# Intelligent_Agriculture.net
KiCad netlist of a schematic drawn in Altium Designer
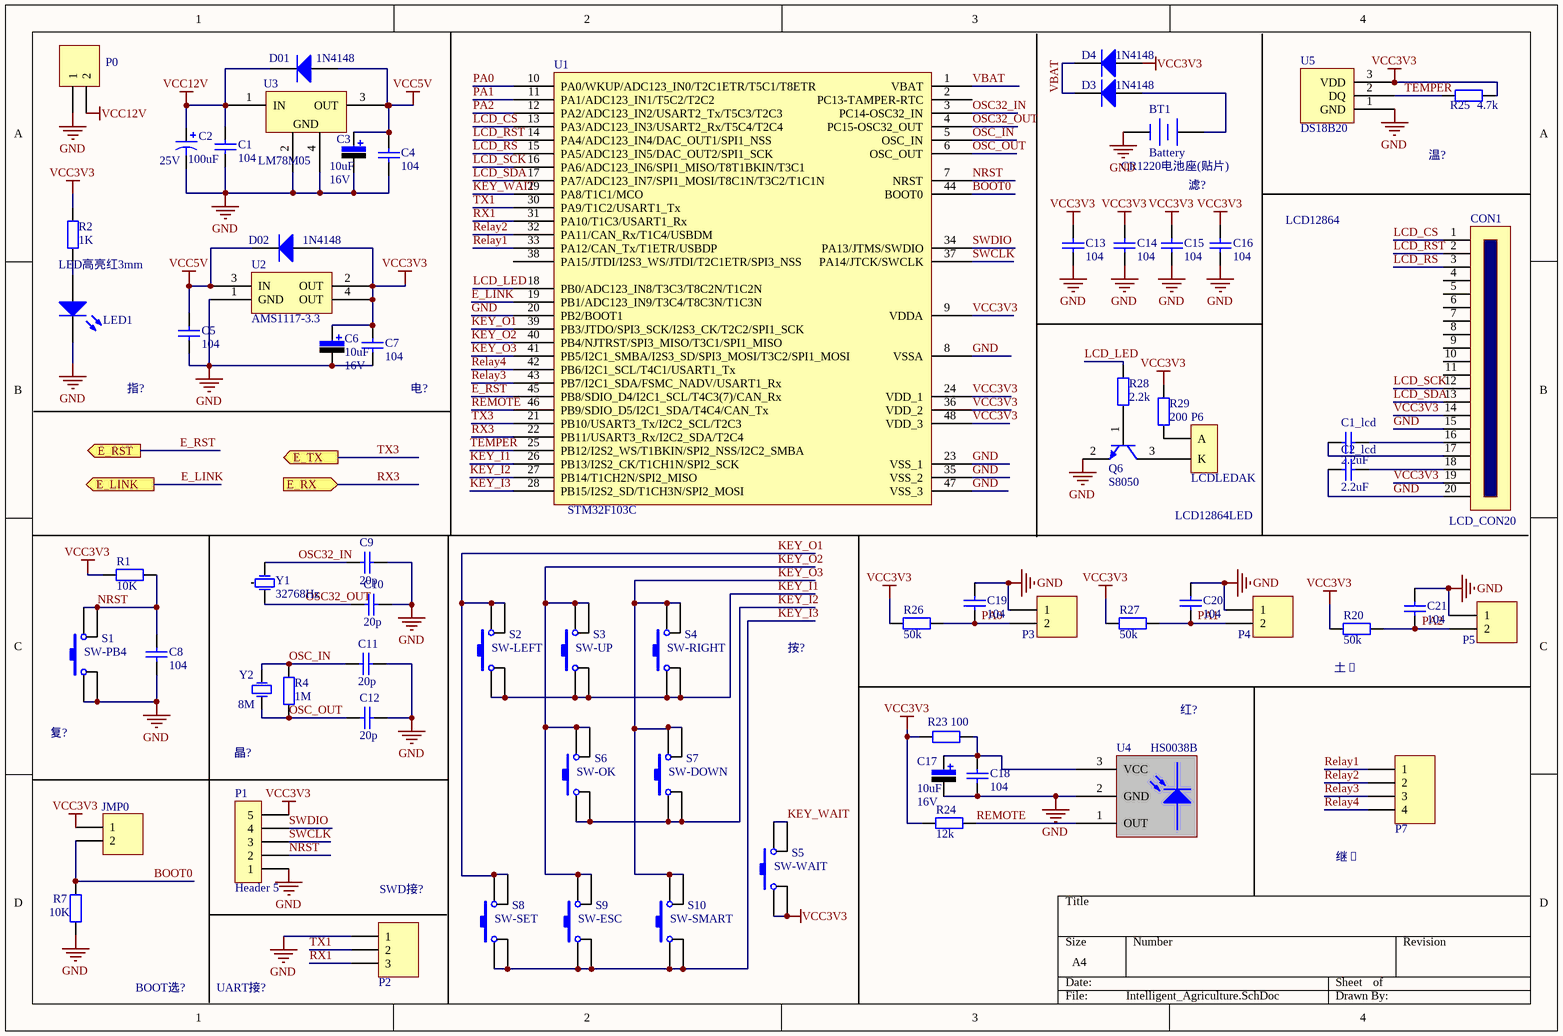
[diagram p0: Intelligent_Agriculture.SchDoc]

(export (version "E")
  (design (tool "Eeschema 10.0.6"))
  (components
    (comp (ref "BT1")
      (value "Battery")
      (description "备份电池")
      (fields (field (name "PUBLISHER") "Altium Limited"))
      (libsource (lib "fszhang") (part "Battery"))
    )
    (comp (ref "C1")
      (value "104")
      (footprint "C-RAD-0805")
      (description "无极性电容")
      (fields (field (name "Comment") "Cap") (field (name "PUBLISHER") "Altium Limited"))
      (libsource (lib "Intelligent_Agriculture_Lib") (part "Cap"))
    )
    (comp (ref "C1_lcd")
      (value "2.2uF")
      (footprint "C-RAD-0805")
      (description "无极性电容")
      (fields (field (name "Comment") "Cap") (field (name "PUBLISHER") "Altium Limited"))
      (libsource (lib "Intelligent_Agriculture_Lib") (part "Cap"))
    )
    (comp (ref "C2")
      (value "100uF")
      (footprint "C-RB-2.54")
      (description "电解电容")
      (fields
        (field (name "VOL") "25V")
        (field (name "Comment") "Cap Pol1")
        (field (name "PUBLISHER") "Altium Limited")
      )
      (libsource (lib "Miscellaneous Devices") (part "Cap Pol1"))
    )
    (comp (ref "C2_lcd")
      (value "2.2uF")
      (footprint "C-RAD-0805")
      (description "无极性电容")
      (fields (field (name "Comment") "Cap") (field (name "PUBLISHER") "Altium Limited"))
      (libsource (lib "Intelligent_Agriculture_Lib") (part "Cap"))
    )
    (comp (ref "C3")
      (value "10uF")
      (footprint "CAP-3528")
      (description "钽电容")
      (fields
        (field (name "VOL") "16V")
        (field (name "Comment") "Cap Pol")
        (field (name "PUBLISHER") "Altium Limited")
      )
      (libsource (lib "Intelligent_Agriculture_Lib") (part "Cap Pol"))
    )
    (comp (ref "C4")
      (value "104")
      (footprint "C-RAD-0805")
      (description "无极性电容")
      (fields (field (name "Comment") "Cap") (field (name "PUBLISHER") "Altium Limited"))
      (libsource (lib "Intelligent_Agriculture_Lib") (part "Cap"))
    )
    (comp (ref "C5")
      (value "104")
      (footprint "C-RAD-0805")
      (description "无极性电容")
      (fields (field (name "Comment") "Cap") (field (name "PUBLISHER") "Altium Limited"))
      (libsource (lib "Intelligent_Agriculture_Lib") (part "Cap"))
    )
    (comp (ref "C6")
      (value "10uF")
      (footprint "CAP-3528")
      (description "钽电容")
      (fields
        (field (name "VOL") "16V")
        (field (name "Comment") "Cap Pol")
        (field (name "PUBLISHER") "Altium Limited")
      )
      (libsource (lib "Intelligent_Agriculture_Lib") (part "Cap Pol"))
    )
    (comp (ref "C7")
      (value "104")
      (footprint "C-RAD-0805")
      (description "无极性电容")
      (fields (field (name "Comment") "Cap") (field (name "PUBLISHER") "Altium Limited"))
      (libsource (lib "Intelligent_Agriculture_Lib") (part "Cap"))
    )
    (comp (ref "C8")
      (value "104")
      (footprint "C-RAD-0805")
      (description "无极性电容")
      (fields (field (name "Comment") "Cap") (field (name "PUBLISHER") "Altium Limited"))
      (libsource (lib "Intelligent_Agriculture_Lib") (part "Cap"))
    )
    (comp (ref "C9")
      (value "20p")
      (footprint "C-RAD-0805")
      (description "无极性电容")
      (fields (field (name "Comment") "Cap") (field (name "PUBLISHER") "Altium Limited"))
      (libsource (lib "Intelligent_Agriculture_Lib") (part "Cap"))
    )
    (comp (ref "C10")
      (value "20p")
      (footprint "C-RAD-0805")
      (description "无极性电容")
      (fields (field (name "Comment") "Cap") (field (name "PUBLISHER") "Altium Limited"))
      (libsource (lib "Intelligent_Agriculture_Lib") (part "Cap"))
    )
    (comp (ref "C11")
      (value "20p")
      (footprint "C-RAD-0805")
      (description "无极性电容")
      (fields (field (name "Comment") "Cap") (field (name "PUBLISHER") "Altium Limited"))
      (libsource (lib "Intelligent_Agriculture_Lib") (part "Cap"))
    )
    (comp (ref "C12")
      (value "20p")
      (footprint "C-RAD-0805")
      (description "无极性电容")
      (fields (field (name "Comment") "Cap") (field (name "PUBLISHER") "Altium Limited"))
      (libsource (lib "Intelligent_Agriculture_Lib") (part "Cap"))
    )
    (comp (ref "C13")
      (value "104")
      (footprint "C-RAD-0805")
      (description "无极性电容")
      (fields (field (name "Comment") "Cap") (field (name "PUBLISHER") "Altium Limited"))
      (libsource (lib "Intelligent_Agriculture_Lib") (part "Cap"))
    )
    (comp (ref "C14")
      (value "104")
      (footprint "C-RAD-0805")
      (description "无极性电容")
      (fields (field (name "Comment") "Cap") (field (name "PUBLISHER") "Altium Limited"))
      (libsource (lib "Intelligent_Agriculture_Lib") (part "Cap"))
    )
    (comp (ref "C15")
      (value "104")
      (footprint "C-RAD-0805")
      (description "无极性电容")
      (fields (field (name "Comment") "Cap") (field (name "PUBLISHER") "Altium Limited"))
      (libsource (lib "Intelligent_Agriculture_Lib") (part "Cap"))
    )
    (comp (ref "C16")
      (value "104")
      (footprint "C-RAD-0805")
      (description "无极性电容")
      (fields (field (name "Comment") "Cap") (field (name "PUBLISHER") "Altium Limited"))
      (libsource (lib "Intelligent_Agriculture_Lib") (part "Cap"))
    )
    (comp (ref "C17")
      (value "10uF")
      (footprint "CAP-3528")
      (description "钽电容")
      (fields
        (field (name "VOL") "16V")
        (field (name "Comment") "Cap Pol")
        (field (name "PUBLISHER") "Altium Limited")
      )
      (libsource (lib "Intelligent_Agriculture_Lib") (part "Cap Pol"))
    )
    (comp (ref "C18")
      (value "104")
      (footprint "C-RAD-0805")
      (description "无极性电容")
      (fields (field (name "Comment") "Cap") (field (name "PUBLISHER") "Altium Limited"))
      (libsource (lib "Intelligent_Agriculture_Lib") (part "Cap"))
    )
    (comp (ref "C19")
      (value "104")
      (footprint "C-RAD-0805")
      (description "无极性电容")
      (fields (field (name "Comment") "Cap") (field (name "PUBLISHER") "Altium Limited"))
      (libsource (lib "Intelligent_Agriculture_Lib") (part "Cap"))
    )
    (comp (ref "C20")
      (value "104")
      (footprint "C-RAD-0805")
      (description "无极性电容")
      (fields (field (name "Comment") "Cap") (field (name "PUBLISHER") "Altium Limited"))
      (libsource (lib "Intelligent_Agriculture_Lib") (part "Cap"))
    )
    (comp (ref "C21")
      (value "104")
      (footprint "C-RAD-0805")
      (description "无极性电容")
      (fields (field (name "Comment") "Cap") (field (name "PUBLISHER") "Altium Limited"))
      (libsource (lib "Intelligent_Agriculture_Lib") (part "Cap"))
    )
    (comp (ref "CON1")
      (value "LCD_CON20")
      (footprint "FPC0.5-20P-A")
      (description "LCD接插件")
      (libsource (lib "fszhang") (part "LCD_CON20"))
    )
    (comp (ref "D01")
      (value "1N4148")
      (footprint "DIODE-1206")
      (description "二极管")
      (fields (field (name "Comment") "Diode") (field (name "PUBLISHER") "Altium Limited"))
      (libsource (lib "Intelligent_Agriculture_Lib") (part "Diode"))
    )
    (comp (ref "D02")
      (value "1N4148")
      (footprint "DIODE-1206")
      (description "二极管")
      (fields (field (name "Comment") "Diode") (field (name "PUBLISHER") "Altium Limited"))
      (libsource (lib "Intelligent_Agriculture_Lib") (part "Diode"))
    )
    (comp (ref "D3")
      (value "1N4148")
      (footprint "DIODE-1206")
      (description "二极管")
      (fields (field (name "Comment") "Diode") (field (name "PUBLISHER") "Altium Limited"))
      (libsource (lib "Intelligent_Agriculture_Lib") (part "Diode"))
    )
    (comp (ref "D4")
      (value "1N4148")
      (footprint "DIODE-1206")
      (description "二极管")
      (fields (field (name "Comment") "Diode") (field (name "PUBLISHER") "Altium Limited"))
      (libsource (lib "Intelligent_Agriculture_Lib") (part "Diode"))
    )
    (comp (ref "JMP0")
      (value "Header 2")
      (footprint "HDR2X1_A")
      (description "接插件")
      (fields (field (name "PUBLISHER") "Altium Limited"))
      (libsource (lib "fszhang") (part "Header 2"))
    )
    (comp (ref "LED1")
      (value "LED0")
      (footprint "LED_A2")
      (description "发光二极管")
      (fields (field (name "PUBLISHER") "Altium Limited"))
      (libsource (lib "Intelligent_Agriculture_Lib") (part "LED0"))
    )
    (comp (ref "P0")
      (value "Header 2")
      (footprint "HDR2X1_B1")
      (description "接插件")
      (fields (field (name "PUBLISHER") "Altium Limited"))
      (libsource (lib "") (part "Header 2_1"))
    )
    (comp (ref "P1")
      (value "Header 5")
      (footprint "HDR5_A1")
      (description "接插件")
      (fields (field (name "PUBLISHER") "Altium Limited"))
      (libsource (lib "fszhang") (part "Header 5"))
    )
    (comp (ref "P2")
      (value "Header 3")
      (footprint "HDR3X1_A")
      (description "接插件")
      (fields (field (name "PUBLISHER") "Altium Limited"))
      (libsource (lib "fszhang") (part "Header 3"))
    )
    (comp (ref "P3")
      (value "Header 2")
      (footprint "HDR2X1_B1")
      (description "接插件")
      (fields (field (name "PUBLISHER") "Altium Limited"))
      (libsource (lib "fszhang") (part "Header 2"))
    )
    (comp (ref "P4")
      (value "Header 2")
      (footprint "HDR2X1_B1")
      (description "接插件")
      (fields (field (name "PUBLISHER") "Altium Limited"))
      (libsource (lib "fszhang") (part "Header 2"))
    )
    (comp (ref "P5")
      (value "Header 2")
      (footprint "HDR2X1_B1")
      (description "接插件")
      (fields (field (name "PUBLISHER") "Altium Limited"))
      (libsource (lib "fszhang") (part "Header 2"))
    )
    (comp (ref "P6")
      (value "LCDLEDAK")
      (footprint "LCD_JLX12864G-1504")
      (description "LCD12864框架")
      (libsource (lib "fszhang") (part "LCDLEDAK"))
    )
    (comp (ref "P7")
      (value "Header 4")
      (footprint "HDR4X1_B1")
      (description "接插件")
      (fields (field (name "PUBLISHER") "Altium Limited"))
      (libsource (lib "fszhang") (part "Header 4"))
    )
    (comp (ref "Q6")
      (value "S8050")
      (description "NPN三极管")
      (fields (field (name "PUBLISHER") "Altium Limited"))
      (libsource (lib "fszhang") (part "BCP68"))
    )
    (comp (ref "R1")
      (value "10K")
      (description "贴片电阻")
      (fields (field (name "Comment") "Res1") (field (name "PUBLISHER") "Altium Limited"))
      (libsource (lib "fszhang") (part "Res1"))
    )
    (comp (ref "R2")
      (value "1K")
      (description "贴片电阻")
      (fields (field (name "Comment") "Res1") (field (name "PUBLISHER") "Altium Limited"))
      (libsource (lib "") (part "Res1_1"))
    )
    (comp (ref "R4")
      (value "1M")
      (description "贴片电阻")
      (fields (field (name "Comment") "Res1") (field (name "PUBLISHER") "Altium Limited"))
      (libsource (lib "") (part "Res1_1"))
    )
    (comp (ref "R7")
      (value "10K")
      (description "贴片电阻")
      (fields (field (name "Comment") "Res1") (field (name "PUBLISHER") "Altium Limited"))
      (libsource (lib "") (part "Res1_2"))
    )
    (comp (ref "R20")
      (value "50k")
      (description "贴片电阻")
      (fields (field (name "Comment") "Res1") (field (name "PUBLISHER") "Altium Limited"))
      (libsource (lib "fszhang") (part "Res1"))
    )
    (comp (ref "R23")
      (value "100")
      (description "贴片电阻")
      (fields (field (name "Comment") "Res1") (field (name "PUBLISHER") "Altium Limited"))
      (libsource (lib "") (part "Res1_3"))
    )
    (comp (ref "R24")
      (value "12k")
      (description "贴片电阻")
      (fields (field (name "Comment") "Res1") (field (name "PUBLISHER") "Altium Limited"))
      (libsource (lib "") (part "Res1_3"))
    )
    (comp (ref "R25")
      (value "4.7k")
      (description "贴片电阻")
      (fields (field (name "Comment") "Res1") (field (name "PUBLISHER") "Altium Limited"))
      (libsource (lib "") (part "Res1_3"))
    )
    (comp (ref "R26")
      (value "50k")
      (description "贴片电阻")
      (fields (field (name "Comment") "Res1") (field (name "PUBLISHER") "Altium Limited"))
      (libsource (lib "fszhang") (part "Res1"))
    )
    (comp (ref "R27")
      (value "50k")
      (description "贴片电阻")
      (fields (field (name "Comment") "Res1") (field (name "PUBLISHER") "Altium Limited"))
      (libsource (lib "fszhang") (part "Res1"))
    )
    (comp (ref "R28")
      (value "2.2k")
      (description "贴片电阻")
      (fields (field (name "Comment") "Res1") (field (name "PUBLISHER") "Altium Limited"))
      (libsource (lib "") (part "Res1_1"))
    )
    (comp (ref "R29")
      (value "200")
      (footprint "1206")
      (description "贴片电阻")
      (fields (field (name "Comment") "Res1") (field (name "PUBLISHER") "Altium Limited"))
      (libsource (lib "") (part "Res1_1"))
    )
    (comp (ref "S1")
      (value "SW-PB4")
      (footprint "SW_PB4_B1")
      (description "微动开关")
      (fields (field (name "PUBLISHER") "Altium Limited"))
      (libsource (lib "fszhang") (part "SW-PB4"))
    )
    (comp (ref "S2")
      (value "SW-LEFT")
      (footprint "SW_PB4_B1")
      (description "微动开关")
      (fields (field (name "PUBLISHER") "Altium Limited"))
      (libsource (lib "fszhang") (part "SW-PB4"))
    )
    (comp (ref "S3")
      (value "SW-UP")
      (footprint "SW_PB4_B1")
      (description "微动开关")
      (fields (field (name "PUBLISHER") "Altium Limited"))
      (libsource (lib "fszhang") (part "SW-PB4"))
    )
    (comp (ref "S4")
      (value "SW-RIGHT")
      (footprint "SW_PB4_B1")
      (description "微动开关")
      (fields (field (name "PUBLISHER") "Altium Limited"))
      (libsource (lib "fszhang") (part "SW-PB4"))
    )
    (comp (ref "S5")
      (value "SW-WAIT")
      (footprint "SW_PB4_B1")
      (description "微动开关")
      (fields (field (name "PUBLISHER") "Altium Limited"))
      (libsource (lib "fszhang") (part "SW-PB4"))
    )
    (comp (ref "S6")
      (value "SW-OK")
      (footprint "SW_PB4_B1")
      (description "微动开关")
      (fields (field (name "PUBLISHER") "Altium Limited"))
      (libsource (lib "fszhang") (part "SW-PB4"))
    )
    (comp (ref "S7")
      (value "SW-DOWN")
      (footprint "SW_PB4_B1")
      (description "微动开关")
      (fields (field (name "PUBLISHER") "Altium Limited"))
      (libsource (lib "fszhang") (part "SW-PB4"))
    )
    (comp (ref "S8")
      (value "SW-SET")
      (footprint "SW_PB4_B1")
      (description "微动开关")
      (fields (field (name "PUBLISHER") "Altium Limited"))
      (libsource (lib "fszhang") (part "SW-PB4"))
    )
    (comp (ref "S9")
      (value "SW-ESC")
      (footprint "SW_PB4_B1")
      (description "微动开关")
      (fields (field (name "PUBLISHER") "Altium Limited"))
      (libsource (lib "fszhang") (part "SW-PB4"))
    )
    (comp (ref "S10")
      (value "SW-SMART")
      (footprint "SW_PB4_B1")
      (description "微动开关")
      (fields (field (name "PUBLISHER") "Altium Limited"))
      (libsource (lib "fszhang") (part "SW-PB4"))
    )
    (comp (ref "U1")
      (value "STM32F103C")
      (footprint "LQFP-48_M")
      (description "STM32单片机48引脚")
      (libsource (lib "fszhang") (part "STM32F103C"))
    )
    (comp (ref "U2")
      (value "AMS1117-3.3")
      (footprint "SOT-223")
      (description "3.3V稳压芯片")
      (libsource (lib "fszhang") (part "SPX1117M3-3.3"))
    )
    (comp (ref "U3")
      (value "LM78M05")
      (footprint "TO-252")
      (description "5V稳压芯片")
      (libsource (lib "fszhang") (part "LM78M05"))
    )
    (comp (ref "U4") (value "HS0038B") (description "红外接收器") (libsource (lib "fszhang") (part "HS0038B")))
    (comp (ref "U5")
      (value "DS18B20")
      (footprint "HDR3X1_B1")
      (description "温度传感器")
      (libsource (lib "fszhang") (part "DS18B20"))
    )
    (comp (ref "Y1")
      (value "32768Hz")
      (footprint "X-TC15_B")
      (description "圆柱晶振")
      (fields (field (name "Comment") "XTAL_SM") (field (name "PUBLISHER") "Altium Limited"))
      (libsource (lib "Intelligent_Agriculture_Lib") (part "XTAL_SM"))
    )
    (comp (ref "Y2")
      (value "8M")
      (description "晶振")
      (fields (field (name "Comment") "XTAL") (field (name "PUBLISHER") "Altium Limited"))
      (libsource (lib "fszhang") (part "XTAL"))
    )
  )
  (nets
    (net (code "1") (name "/BOOT0") (class "Default")
      (node (ref "JMP0") (pin "2") (pinfunction "2_2") (pintype "passive"))
      (node (ref "R7") (pin "1") (pinfunction "1_1") (pintype "passive"))
      (node (ref "U1") (pin "44") (pinfunction "BOOT0_44") (pintype "passive"))
    )
    (net (code "2") (name "/E_LINK") (class "Default")
      (node (ref "U1") (pin "19") (pinfunction "PB1/ADC123_IN9/T3C4/T8C3N/T1C3N_19") (pintype "passive"))
    )
    (net (code "3") (name "/E_RST") (class "Default")
      (node (ref "U1") (pin "45") (pinfunction "PB8/SDIO_D4/I2C1_SCL/T4C3(7)/CAN_Rx_45") (pintype "passive"))
    )
    (net (code "4") (name "/KEY_I1") (class "Default")
      (node (ref "S2") (pin "1") (pinfunction "1_1") (pintype "passive"))
      (node (ref "S2") (pin "4") (pinfunction "4_4") (pintype "passive"))
      (node (ref "S3") (pin "1") (pinfunction "1_1") (pintype "passive"))
      (node (ref "S3") (pin "4") (pinfunction "4_4") (pintype "passive"))
      (node (ref "S4") (pin "1") (pinfunction "1_1") (pintype "passive"))
      (node (ref "S4") (pin "4") (pinfunction "4_4") (pintype "passive"))
      (node (ref "U1") (pin "26") (pinfunction "PB13/I2S2_CK/T1CH1N/SPI2_SCK_26") (pintype "passive"))
    )
    (net (code "5") (name "/KEY_I2") (class "Default")
      (node (ref "S6") (pin "1") (pinfunction "1_1") (pintype "passive"))
      (node (ref "S6") (pin "4") (pinfunction "4_4") (pintype "passive"))
      (node (ref "S7") (pin "1") (pinfunction "1_1") (pintype "passive"))
      (node (ref "S7") (pin "4") (pinfunction "4_4") (pintype "passive"))
      (node (ref "U1") (pin "27") (pinfunction "PB14/T1CH2N/SPI2_MISO_27") (pintype "passive"))
    )
    (net (code "6") (name "/KEY_I3") (class "Default")
      (node (ref "S10") (pin "1") (pinfunction "1_1") (pintype "passive"))
      (node (ref "S10") (pin "4") (pinfunction "4_4") (pintype "passive"))
      (node (ref "S8") (pin "1") (pinfunction "1_1") (pintype "passive"))
      (node (ref "S8") (pin "4") (pinfunction "4_4") (pintype "passive"))
      (node (ref "S9") (pin "1") (pinfunction "1_1") (pintype "passive"))
      (node (ref "S9") (pin "4") (pinfunction "4_4") (pintype "passive"))
      (node (ref "U1") (pin "28") (pinfunction "PB15/I2S2_SD/T1CH3N/SPI2_MOSI_28") (pintype "passive"))
    )
    (net (code "7") (name "/KEY_O1") (class "Default")
      (node (ref "S2") (pin "2") (pinfunction "2_2") (pintype "passive"))
      (node (ref "S2") (pin "3") (pinfunction "3_3") (pintype "passive"))
      (node (ref "S8") (pin "2") (pinfunction "2_2") (pintype "passive"))
      (node (ref "S8") (pin "3") (pinfunction "3_3") (pintype "passive"))
      (node (ref "U1") (pin "39") (pinfunction "PB3/JTDO/SPI3_SCK/I2S3_CK/T2C2/SPI1_SCK_39") (pintype "passive"))
    )
    (net (code "8") (name "/KEY_O2") (class "Default")
      (node (ref "S3") (pin "2") (pinfunction "2_2") (pintype "passive"))
      (node (ref "S3") (pin "3") (pinfunction "3_3") (pintype "passive"))
      (node (ref "S6") (pin "2") (pinfunction "2_2") (pintype "passive"))
      (node (ref "S6") (pin "3") (pinfunction "3_3") (pintype "passive"))
      (node (ref "S9") (pin "2") (pinfunction "2_2") (pintype "passive"))
      (node (ref "S9") (pin "3") (pinfunction "3_3") (pintype "passive"))
      (node (ref "U1") (pin "40") (pinfunction "PB4/NJTRST/SPI3_MISO/T3C1/SPI1_MISO_40") (pintype "passive"))
    )
    (net (code "9") (name "/KEY_O3") (class "Default")
      (node (ref "S10") (pin "2") (pinfunction "2_2") (pintype "passive"))
      (node (ref "S10") (pin "3") (pinfunction "3_3") (pintype "passive"))
      (node (ref "S4") (pin "2") (pinfunction "2_2") (pintype "passive"))
      (node (ref "S4") (pin "3") (pinfunction "3_3") (pintype "passive"))
      (node (ref "S7") (pin "2") (pinfunction "2_2") (pintype "passive"))
      (node (ref "S7") (pin "3") (pinfunction "3_3") (pintype "passive"))
      (node (ref "U1") (pin "41") (pinfunction "PB5/I2C1_SMBA/I2S3_SD/SPI3_MOSI/T3C2/SPI1_MOSI_41") (pintype "passive"))
    )
    (net (code "10") (name "/KEY_WAIT") (class "Default")
      (node (ref "S5") (pin "2") (pinfunction "2_2") (pintype "passive"))
      (node (ref "S5") (pin "3") (pinfunction "3_3") (pintype "passive"))
      (node (ref "U1") (pin "29") (pinfunction "PA8/T1C1/MCO_29") (pintype "passive"))
    )
    (net (code "11") (name "/LCD_CS") (class "Default")
      (node (ref "CON1") (pin "1") (pinfunction "1_1") (pintype "passive"))
      (node (ref "U1") (pin "13") (pinfunction "PA3/ADC123_IN3/USART2_Rx/T5C4/T2C4_13") (pintype "passive"))
    )
    (net (code "12") (name "/LCD_LED") (class "Default")
      (node (ref "R28") (pin "2") (pinfunction "2_2") (pintype "passive"))
      (node (ref "U1") (pin "18") (pinfunction "PB0/ADC123_IN8/T3C3/T8C2N/T1C2N_18") (pintype "passive"))
    )
    (net (code "13") (name "/LCD_RS") (class "Default")
      (node (ref "CON1") (pin "3") (pinfunction "3_3") (pintype "passive"))
      (node (ref "U1") (pin "15") (pinfunction "PA5/ADC123_IN5/DAC_OUT2/SPI1_SCK_15") (pintype "passive"))
    )
    (net (code "14") (name "/LCD_RST") (class "Default")
      (node (ref "CON1") (pin "2") (pinfunction "2_2") (pintype "passive"))
      (node (ref "U1") (pin "14") (pinfunction "PA4/ADC123_IN4/DAC_OUT1/SPI1_NSS_14") (pintype "passive"))
    )
    (net (code "15") (name "/LCD_SCK") (class "Default")
      (node (ref "CON1") (pin "12") (pinfunction "12_12") (pintype "passive"))
      (node (ref "U1") (pin "16") (pinfunction "PA6/ADC123_IN6/SPI1_MISO/T8T1BKIN/T3C1_16") (pintype "passive"))
    )
    (net (code "16") (name "/LCD_SDA") (class "Default")
      (node (ref "CON1") (pin "13") (pinfunction "13_13") (pintype "passive"))
      (node (ref "U1") (pin "17") (pinfunction "PA7/ADC123_IN7/SPI1_MOSI/T8C1N/T3C2/T1C1N_17") (pintype "passive"))
    )
    (net (code "17") (name "/NRST") (class "Default")
      (node (ref "C8") (pin "2") (pinfunction "2_2") (pintype "passive"))
      (node (ref "P1") (pin "2") (pinfunction "2_2") (pintype "passive"))
      (node (ref "R1") (pin "1") (pinfunction "1_1") (pintype "passive"))
      (node (ref "S1") (pin "2") (pinfunction "2_2") (pintype "passive"))
      (node (ref "S1") (pin "3") (pinfunction "3_3") (pintype "passive"))
      (node (ref "U1") (pin "7") (pinfunction "NRST_7") (pintype "passive"))
    )
    (net (code "18") (name "/OSC32_IN") (class "Default")
      (node (ref "C9") (pin "1") (pinfunction "1_1") (pintype "passive"))
      (node (ref "U1") (pin "3") (pinfunction "PC14-OSC32_IN_3") (pintype "passive"))
      (node (ref "Y1") (pin "1") (pinfunction "OSC1_1") (pintype "passive"))
    )
    (net (code "19") (name "/OSC32_OUT") (class "Default")
      (node (ref "C10") (pin "1") (pinfunction "1_1") (pintype "passive"))
      (node (ref "U1") (pin "4") (pinfunction "PC15-OSC32_OUT_4") (pintype "passive"))
      (node (ref "Y1") (pin "2") (pinfunction "OSC2_2") (pintype "passive"))
    )
    (net (code "20") (name "/OSC_IN") (class "Default")
      (node (ref "C11") (pin "1") (pinfunction "1_1") (pintype "passive"))
      (node (ref "R4") (pin "2") (pinfunction "2_2") (pintype "passive"))
      (node (ref "U1") (pin "5") (pinfunction "OSC_IN_5") (pintype "passive"))
      (node (ref "Y2") (pin "2") (pinfunction "OSC2_2") (pintype "passive"))
    )
    (net (code "21") (name "/OSC_OUT") (class "Default")
      (node (ref "C12") (pin "1") (pinfunction "1_1") (pintype "passive"))
      (node (ref "R4") (pin "1") (pinfunction "1_1") (pintype "passive"))
      (node (ref "U1") (pin "6") (pinfunction "OSC_OUT_6") (pintype "passive"))
      (node (ref "Y2") (pin "1") (pinfunction "OSC1_1") (pintype "passive"))
    )
    (net (code "22") (name "/PA0") (class "Default")
      (node (ref "C19") (pin "2") (pinfunction "2_2") (pintype "passive"))
      (node (ref "P3") (pin "2") (pinfunction "2_2") (pintype "passive"))
      (node (ref "R26") (pin "1") (pinfunction "1_1") (pintype "passive"))
      (node (ref "U1") (pin "10") (pinfunction "PA0/WKUP/ADC123_IN0/T2C1ETR/T5C1/T8ETR_10") (pintype "passive"))
    )
    (net (code "23") (name "/PA1") (class "Default")
      (node (ref "C20") (pin "2") (pinfunction "2_2") (pintype "passive"))
      (node (ref "P4") (pin "2") (pinfunction "2_2") (pintype "passive"))
      (node (ref "R27") (pin "1") (pinfunction "1_1") (pintype "passive"))
      (node (ref "U1") (pin "11") (pinfunction "PA1/ADC123_IN1/T5C2/T2C2_11") (pintype "passive"))
    )
    (net (code "24") (name "/PA2") (class "Default")
      (node (ref "C21") (pin "2") (pinfunction "2_2") (pintype "passive"))
      (node (ref "P5") (pin "2") (pinfunction "2_2") (pintype "passive"))
      (node (ref "R20") (pin "1") (pinfunction "1_1") (pintype "passive"))
      (node (ref "U1") (pin "12") (pinfunction "PA2/ADC123_IN2/USART2_Tx/T5C3/T2C3_12") (pintype "passive"))
    )
    (net (code "25") (name "/REMOTE") (class "Default")
      (node (ref "R24") (pin "2") (pinfunction "2_2") (pintype "passive"))
      (node (ref "U1") (pin "46") (pinfunction "PB9/SDIO_D5/I2C1_SDA/T4C4/CAN_Tx_46") (pintype "passive"))
      (node (ref "U4") (pin "1") (pinfunction "OUT_1") (pintype "passive"))
    )
    (net (code "26") (name "/RX1") (class "Default")
      (node (ref "P2") (pin "3") (pinfunction "3_3") (pintype "passive"))
      (node (ref "U1") (pin "31") (pinfunction "PA10/T1C3/USART1_Rx_31") (pintype "passive"))
    )
    (net (code "27") (name "/RX3") (class "Default")
      (node (ref "U1") (pin "22") (pinfunction "PB11/USART3_Rx/I2C2_SDA/T2C4_22") (pintype "passive"))
    )
    (net (code "28") (name "/Relay1") (class "Default")
      (node (ref "P7") (pin "1") (pinfunction "1_1") (pintype "passive"))
      (node (ref "U1") (pin "33") (pinfunction "PA12/CAN_Tx/T1ETR/USBDP_33") (pintype "passive"))
    )
    (net (code "29") (name "/Relay2") (class "Default")
      (node (ref "P7") (pin "2") (pinfunction "2_2") (pintype "passive"))
      (node (ref "U1") (pin "32") (pinfunction "PA11/CAN_Rx/T1C4/USBDM_32") (pintype "passive"))
    )
    (net (code "30") (name "/Relay3") (class "Default")
      (node (ref "P7") (pin "3") (pinfunction "3_3") (pintype "passive"))
      (node (ref "U1") (pin "43") (pinfunction "PB7/I2C1_SDA/FSMC_NADV/USART1_Rx_43") (pintype "passive"))
    )
    (net (code "31") (name "/Relay4") (class "Default")
      (node (ref "P7") (pin "4") (pinfunction "4_4") (pintype "passive"))
      (node (ref "U1") (pin "42") (pinfunction "PB6/I2C1_SCL/T4C1/USART1_Tx_42") (pintype "passive"))
    )
    (net (code "32") (name "/SWCLK") (class "Default")
      (node (ref "P1") (pin "3") (pinfunction "3_3") (pintype "passive"))
      (node (ref "U1") (pin "37") (pinfunction "PA14/JTCK/SWCLK_37") (pintype "passive"))
    )
    (net (code "33") (name "/SWDIO") (class "Default")
      (node (ref "P1") (pin "4") (pinfunction "4_4") (pintype "passive"))
      (node (ref "U1") (pin "34") (pinfunction "PA13/JTMS/SWDIO_34") (pintype "passive"))
    )
    (net (code "34") (name "/TEMPER") (class "Default")
      (node (ref "R25") (pin "1") (pinfunction "1_1") (pintype "passive"))
      (node (ref "U1") (pin "25") (pinfunction "PB12/I2S2_WS/T1BKIN/SPI2_NSS/I2C2_SMBA_25") (pintype "passive"))
      (node (ref "U5") (pin "2") (pinfunction "DQ_2") (pintype "passive"))
    )
    (net (code "35") (name "/TX1") (class "Default")
      (node (ref "P2") (pin "2") (pinfunction "2_2") (pintype "passive"))
      (node (ref "U1") (pin "30") (pinfunction "PA9/T1C2/USART1_Tx_30") (pintype "passive"))
    )
    (net (code "36") (name "/TX3") (class "Default")
      (node (ref "U1") (pin "21") (pinfunction "PB10/USART3_Tx/I2C2_SCL/T2C3_21") (pintype "passive"))
    )
    (net (code "37") (name "/VBAT") (class "Default")
      (node (ref "D3") (pin "2") (pinfunction "K_2") (pintype "passive"))
      (node (ref "D4") (pin "2") (pinfunction "K_2") (pintype "passive"))
      (node (ref "U1") (pin "1") (pinfunction "VBAT_1") (pintype "passive"))
    )
    (net (code "38") (name "GND") (class "Default")
      (node (ref "BT1") (pin "2") (pinfunction "-_2") (pintype "passive"))
      (node (ref "C1") (pin "2") (pinfunction "2_2") (pintype "passive"))
      (node (ref "C10") (pin "2") (pinfunction "2_2") (pintype "passive"))
      (node (ref "C11") (pin "2") (pinfunction "2_2") (pintype "passive"))
      (node (ref "C12") (pin "2") (pinfunction "2_2") (pintype "passive"))
      (node (ref "C13") (pin "2") (pinfunction "2_2") (pintype "passive"))
      (node (ref "C14") (pin "2") (pinfunction "2_2") (pintype "passive"))
      (node (ref "C15") (pin "2") (pinfunction "2_2") (pintype "passive"))
      (node (ref "C16") (pin "2") (pinfunction "2_2") (pintype "passive"))
      (node (ref "C17") (pin "2") (pinfunction "2_2") (pintype "passive"))
      (node (ref "C18") (pin "2") (pinfunction "2_2") (pintype "passive"))
      (node (ref "C19") (pin "1") (pinfunction "1_1") (pintype "passive"))
      (node (ref "C2") (pin "2") (pinfunction "2_2") (pintype "passive"))
      (node (ref "C20") (pin "1") (pinfunction "1_1") (pintype "passive"))
      (node (ref "C21") (pin "1") (pinfunction "1_1") (pintype "passive"))
      (node (ref "C2_lcd") (pin "2") (pinfunction "2_2") (pintype "passive"))
      (node (ref "C3") (pin "2") (pinfunction "2_2") (pintype "passive"))
      (node (ref "C4") (pin "2") (pinfunction "2_2") (pintype "passive"))
      (node (ref "C5") (pin "2") (pinfunction "2_2") (pintype "passive"))
      (node (ref "C6") (pin "2") (pinfunction "2_2") (pintype "passive"))
      (node (ref "C7") (pin "2") (pinfunction "2_2") (pintype "passive"))
      (node (ref "C8") (pin "1") (pinfunction "1_1") (pintype "passive"))
      (node (ref "C9") (pin "2") (pinfunction "2_2") (pintype "passive"))
      (node (ref "CON1") (pin "15") (pinfunction "15_15") (pintype "passive"))
      (node (ref "CON1") (pin "20") (pinfunction "20_20") (pintype "passive"))
      (node (ref "LED1") (pin "2") (pinfunction "K_2") (pintype "passive"))
      (node (ref "P0") (pin "1") (pinfunction "1_1") (pintype "passive"))
      (node (ref "P1") (pin "1") (pinfunction "1_1") (pintype "passive"))
      (node (ref "P2") (pin "1") (pinfunction "1_1") (pintype "passive"))
      (node (ref "P3") (pin "1") (pinfunction "1_1") (pintype "passive"))
      (node (ref "P4") (pin "1") (pinfunction "1_1") (pintype "passive"))
      (node (ref "P5") (pin "1") (pinfunction "1_1") (pintype "passive"))
      (node (ref "Q6") (pin "2") (pinfunction "E_2") (pintype "passive"))
      (node (ref "R7") (pin "2") (pinfunction "2_2") (pintype "passive"))
      (node (ref "S1") (pin "1") (pinfunction "1_1") (pintype "passive"))
      (node (ref "S1") (pin "4") (pinfunction "4_4") (pintype "passive"))
      (node (ref "U1") (pin "20") (pinfunction "PB2/BOOT1_20") (pintype "passive"))
      (node (ref "U1") (pin "23") (pinfunction "VSS_1_23") (pintype "passive"))
      (node (ref "U1") (pin "35") (pinfunction "VSS_2_35") (pintype "passive"))
      (node (ref "U1") (pin "47") (pinfunction "VSS_3_47") (pintype "passive"))
      (node (ref "U1") (pin "8") (pinfunction "VSSA_8") (pintype "passive"))
      (node (ref "U2") (pin "1") (pinfunction "GND_1") (pintype "passive"))
      (node (ref "U3") (pin "2") (pinfunction "GND_2") (pintype "power_in"))
      (node (ref "U3") (pin "4") (pinfunction "GND_4") (pintype "power_in"))
      (node (ref "U4") (pin "2") (pinfunction "GND_2") (pintype "passive"))
      (node (ref "U5") (pin "1") (pinfunction "GND_1") (pintype "passive"))
    )
    (net (code "39") (name "Net-(BT1-+)") (class "Default")
      (node (ref "BT1") (pin "1") (pinfunction "+_1") (pintype "passive"))
      (node (ref "D3") (pin "1") (pinfunction "A_1") (pintype "passive"))
    )
    (net (code "40") (name "Net-(C1_lcd-Pad1)") (class "Default")
      (node (ref "C1_lcd") (pin "1") (pinfunction "1_1") (pintype "passive"))
      (node (ref "CON1") (pin "16") (pinfunction "16_16") (pintype "passive"))
    )
    (net (code "41") (name "Net-(C1_lcd-Pad2)") (class "Default")
      (node (ref "C1_lcd") (pin "2") (pinfunction "2_2") (pintype "passive"))
      (node (ref "CON1") (pin "17") (pinfunction "17_17") (pintype "passive"))
    )
    (net (code "42") (name "Net-(C2_lcd-Pad1)") (class "Default")
      (node (ref "C2_lcd") (pin "1") (pinfunction "1_1") (pintype "passive"))
      (node (ref "CON1") (pin "18") (pinfunction "18_18") (pintype "passive"))
    )
    (net (code "43") (name "Net-(LED1-A)") (class "Default")
      (node (ref "LED1") (pin "1") (pinfunction "A_1") (pintype "passive"))
      (node (ref "R2") (pin "1") (pinfunction "1_1") (pintype "passive"))
    )
    (net (code "44") (name "Net-(P6-A)") (class "Default")
      (node (ref "P6") (pin "1") (pinfunction "A_1") (pintype "passive"))
      (node (ref "R29") (pin "1") (pinfunction "1_1") (pintype "passive"))
    )
    (net (code "45") (name "Net-(P6-K)") (class "Default")
      (node (ref "P6") (pin "2") (pinfunction "K_2") (pintype "passive"))
      (node (ref "Q6") (pin "3") (pinfunction "C_3") (pintype "passive"))
    )
    (net (code "46") (name "Net-(Q6-B)") (class "Default")
      (node (ref "Q6") (pin "1") (pinfunction "B_1") (pintype "passive"))
      (node (ref "R28") (pin "1") (pinfunction "1_1") (pintype "passive"))
    )
    (net (code "47") (name "Net-(U4-VCC)") (class "Default")
      (node (ref "C17") (pin "1") (pinfunction "1_1") (pintype "passive"))
      (node (ref "C18") (pin "1") (pinfunction "1_1") (pintype "passive"))
      (node (ref "R23") (pin "2") (pinfunction "2_2") (pintype "passive"))
      (node (ref "U4") (pin "3") (pinfunction "VCC_3") (pintype "passive"))
    )
    (net (code "48") (name "VCC3V3") (class "Default")
      (node (ref "C13") (pin "1") (pinfunction "1_1") (pintype "passive"))
      (node (ref "C14") (pin "1") (pinfunction "1_1") (pintype "passive"))
      (node (ref "C15") (pin "1") (pinfunction "1_1") (pintype "passive"))
      (node (ref "C16") (pin "1") (pinfunction "1_1") (pintype "passive"))
      (node (ref "C6") (pin "1") (pinfunction "1_1") (pintype "passive"))
      (node (ref "C7") (pin "1") (pinfunction "1_1") (pintype "passive"))
      (node (ref "CON1") (pin "14") (pinfunction "14_14") (pintype "passive"))
      (node (ref "CON1") (pin "19") (pinfunction "19_19") (pintype "passive"))
      (node (ref "D02") (pin "1") (pinfunction "A_1") (pintype "passive"))
      (node (ref "D4") (pin "1") (pinfunction "A_1") (pintype "passive"))
      (node (ref "JMP0") (pin "1") (pinfunction "1_1") (pintype "passive"))
      (node (ref "P1") (pin "5") (pinfunction "5_5") (pintype "passive"))
      (node (ref "R1") (pin "2") (pinfunction "2_2") (pintype "passive"))
      (node (ref "R2") (pin "2") (pinfunction "2_2") (pintype "passive"))
      (node (ref "R20") (pin "2") (pinfunction "2_2") (pintype "passive"))
      (node (ref "R23") (pin "1") (pinfunction "1_1") (pintype "passive"))
      (node (ref "R24") (pin "1") (pinfunction "1_1") (pintype "passive"))
      (node (ref "R25") (pin "2") (pinfunction "2_2") (pintype "passive"))
      (node (ref "R26") (pin "2") (pinfunction "2_2") (pintype "passive"))
      (node (ref "R27") (pin "2") (pinfunction "2_2") (pintype "passive"))
      (node (ref "R29") (pin "2") (pinfunction "2_2") (pintype "passive"))
      (node (ref "S5") (pin "1") (pinfunction "1_1") (pintype "passive"))
      (node (ref "S5") (pin "4") (pinfunction "4_4") (pintype "passive"))
      (node (ref "U1") (pin "24") (pinfunction "VDD_1_24") (pintype "passive"))
      (node (ref "U1") (pin "36") (pinfunction "VDD_2_36") (pintype "passive"))
      (node (ref "U1") (pin "48") (pinfunction "VDD_3_48") (pintype "passive"))
      (node (ref "U1") (pin "9") (pinfunction "VDDA_9") (pintype "passive"))
      (node (ref "U2") (pin "2") (pinfunction "OUT_2") (pintype "passive"))
      (node (ref "U2") (pin "4") (pinfunction "OUT_4") (pintype "passive"))
      (node (ref "U5") (pin "3") (pinfunction "VDD_3") (pintype "passive"))
    )
    (net (code "49") (name "VCC5V") (class "Default")
      (node (ref "C3") (pin "1") (pinfunction "1_1") (pintype "passive"))
      (node (ref "C4") (pin "1") (pinfunction "1_1") (pintype "passive"))
      (node (ref "C5") (pin "1") (pinfunction "1_1") (pintype "passive"))
      (node (ref "D01") (pin "1") (pinfunction "A_1") (pintype "passive"))
      (node (ref "D02") (pin "2") (pinfunction "K_2") (pintype "passive"))
      (node (ref "U2") (pin "3") (pinfunction "IN_3") (pintype "passive"))
      (node (ref "U3") (pin "3") (pinfunction "OUT_3") (pintype "power_in"))
    )
    (net (code "50") (name "VCC12V") (class "Default")
      (node (ref "C1") (pin "1") (pinfunction "1_1") (pintype "passive"))
      (node (ref "C2") (pin "1") (pinfunction "1_1") (pintype "passive"))
      (node (ref "D01") (pin "2") (pinfunction "K_2") (pintype "passive"))
      (node (ref "P0") (pin "2") (pinfunction "2_2") (pintype "passive"))
      (node (ref "U3") (pin "1") (pinfunction "IN_1") (pintype "power_in"))
    )
    (net (code "51") (name "unconnected-(CON1-Pad4)") (class "Default")
      (node (ref "CON1") (pin "4") (pinfunction "4_4") (pintype "passive"))
    )
    (net (code "52") (name "unconnected-(CON1-Pad5)") (class "Default")
      (node (ref "CON1") (pin "5") (pinfunction "5_5") (pintype "passive"))
    )
    (net (code "53") (name "unconnected-(CON1-Pad6)") (class "Default")
      (node (ref "CON1") (pin "6") (pinfunction "6_6") (pintype "passive"))
    )
    (net (code "54") (name "unconnected-(CON1-Pad7)") (class "Default")
      (node (ref "CON1") (pin "7") (pinfunction "7_7") (pintype "passive"))
    )
    (net (code "55") (name "unconnected-(CON1-Pad8)") (class "Default")
      (node (ref "CON1") (pin "8") (pinfunction "8_8") (pintype "passive"))
    )
    (net (code "56") (name "unconnected-(CON1-Pad9)") (class "Default")
      (node (ref "CON1") (pin "9") (pinfunction "9_9") (pintype "passive"))
    )
    (net (code "57") (name "unconnected-(CON1-Pad10)") (class "Default")
      (node (ref "CON1") (pin "10") (pinfunction "10_10") (pintype "passive"))
    )
    (net (code "58") (name "unconnected-(CON1-Pad11)") (class "Default")
      (node (ref "CON1") (pin "11") (pinfunction "11_11") (pintype "passive"))
    )
    (net (code "59") (name "unconnected-(U1-PA15{slash}JTDI{slash}I2S3_WS{slash}JTDI{slash}T2C1ETR{slash}SPI3_NSS-Pad38)") (class "Default")
      (node (ref "U1") (pin "38") (pinfunction "PA15/JTDI/I2S3_WS/JTDI/T2C1ETR/SPI3_NSS_38") (pintype "passive"))
    )
    (net (code "60") (name "unconnected-(U1-PC13-TAMPER-RTC-Pad2)") (class "Default")
      (node (ref "U1") (pin "2") (pinfunction "PC13-TAMPER-RTC_2") (pintype "passive"))
    )
    (net (code "61") (name "unconnected-(Y1-Pad3)") (class "Default")
      (node (ref "Y1") (pin "3") (pinfunction "3_3") (pintype "passive"))
    )
  )
)
